# design.net
KiCad netlist of a schematic drawn in Altium Designer
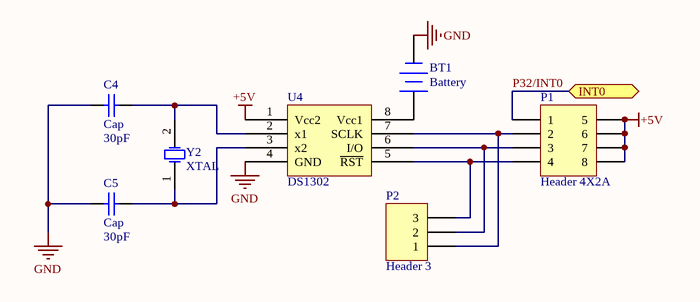
[diagram p0: 时钟电路.SchDoc]

(export (version "E")
  (design (tool "Eeschema 10.0.6"))
  (components
    (comp (ref "BT1")
      (value "Battery")
      (footprint "BAT-2")
      (description "Multicell Battery")
      (fields (field (name "PUBLISHER") "Altium Limited"))
      (libsource (lib "Miscellaneous Devices") (part "Battery"))
    )
    (comp (ref "C4")
      (value "Cap")
      (footprint "RAD-0.3")
      (description "Capacitor")
      (fields (field (name "ALTIUM_VALUE") "30pF") (field (name "PUBLISHER") "Altium Limited"))
      (libsource (lib "Miscellaneous Devices") (part "Cap"))
    )
    (comp (ref "C5")
      (value "Cap")
      (footprint "RAD-0.3")
      (description "Capacitor")
      (fields (field (name "ALTIUM_VALUE") "30pF") (field (name "PUBLISHER") "Altium Limited"))
      (libsource (lib "Miscellaneous Devices") (part "Cap"))
    )
    (comp (ref "P1")
      (value "Header 4X2A")
      (footprint "HDR2X4_CEN")
      (description "Header, 4-Pin, Dual row")
      (fields (field (name "PUBLISHER") "Altium Limited"))
      (libsource (lib "Miscellaneous Connectors") (part "Header 4X2A"))
    )
    (comp (ref "P2")
      (value "Header 3")
      (footprint "HDR1X3")
      (description "Header, 3-Pin")
      (fields (field (name "PUBLISHER") "Altium Limited"))
      (libsource (lib "Miscellaneous Connectors") (part "Header 3"))
    )
    (comp (ref "U4")
      (value "DS1302")
      (footprint "51开发板封装库_W:SOIC127P1030-8L")
      (libsource (lib "51开发板原理图库") (part "DS1302"))
    )
    (comp (ref "Y2")
      (value "XTAL")
      (footprint "R38")
      (description "Crystal Oscillator")
      (fields (field (name "PUBLISHER") "Altium Limited"))
      (libsource (lib "Miscellaneous Devices") (part "XTAL"))
    )
  )
  (nets
    (net (code "1") (name "+5V") (class "Default")
      (node (ref "P1") (pin "5") (pinfunction "5_5") (pintype "passive"))
      (node (ref "P1") (pin "6") (pinfunction "6_6") (pintype "passive"))
      (node (ref "P1") (pin "7") (pinfunction "7_7") (pintype "passive"))
      (node (ref "P1") (pin "8") (pinfunction "8_8") (pintype "passive"))
      (node (ref "U4") (pin "1") (pinfunction "Vcc2_1") (pintype "passive"))
    )
    (net (code "2") (name "/P32{slash}INT0") (class "Default")
      (node (ref "P1") (pin "1") (pinfunction "1_1") (pintype "passive"))
    )
    (net (code "3") (name "GND") (class "Default")
      (node (ref "BT1") (pin "2") (pinfunction "-_2") (pintype "passive"))
      (node (ref "C4") (pin "2") (pinfunction "2_2") (pintype "passive"))
      (node (ref "C5") (pin "1") (pinfunction "1_1") (pintype "passive"))
      (node (ref "U4") (pin "4") (pinfunction "GND_4") (pintype "passive"))
    )
    (net (code "4") (name "Net-(BT1-+)") (class "Default")
      (node (ref "BT1") (pin "1") (pinfunction "+_1") (pintype "passive"))
      (node (ref "U4") (pin "8") (pinfunction "Vcc1_8") (pintype "passive"))
    )
    (net (code "5") (name "Net-(U4-I{slash}O)") (class "Default")
      (node (ref "P1") (pin "3") (pinfunction "3_3") (pintype "passive"))
      (node (ref "P2") (pin "2") (pinfunction "2_2") (pintype "passive"))
      (node (ref "U4") (pin "6") (pinfunction "I/O_6") (pintype "passive"))
    )
    (net (code "6") (name "Net-(U4-SCLK)") (class "Default")
      (node (ref "P1") (pin "2") (pinfunction "2_2") (pintype "passive"))
      (node (ref "P2") (pin "1") (pinfunction "1_1") (pintype "passive"))
      (node (ref "U4") (pin "7") (pinfunction "SCLK_7") (pintype "passive"))
    )
    (net (code "7") (name "Net-(U4-x1)") (class "Default")
      (node (ref "C4") (pin "1") (pinfunction "1_1") (pintype "passive"))
      (node (ref "U4") (pin "2") (pinfunction "x1_2") (pintype "passive"))
      (node (ref "Y2") (pin "2") (pinfunction "OSC2_2") (pintype "passive"))
    )
    (net (code "8") (name "Net-(U4-x2)") (class "Default")
      (node (ref "C5") (pin "2") (pinfunction "2_2") (pintype "passive"))
      (node (ref "U4") (pin "3") (pinfunction "x2_3") (pintype "passive"))
      (node (ref "Y2") (pin "1") (pinfunction "OSC1_1") (pintype "passive"))
    )
    (net (code "9") (name "Net-(U4-~{RST})") (class "Default")
      (node (ref "P1") (pin "4") (pinfunction "4_4") (pintype "passive"))
      (node (ref "P2") (pin "3") (pinfunction "3_3") (pintype "passive"))
      (node (ref "U4") (pin "5") (pinfunction "~{RST}_5") (pintype "passive"))
    )
  )
)
